# pcb.net
KiCad netlist of a schematic drawn in EAGLE
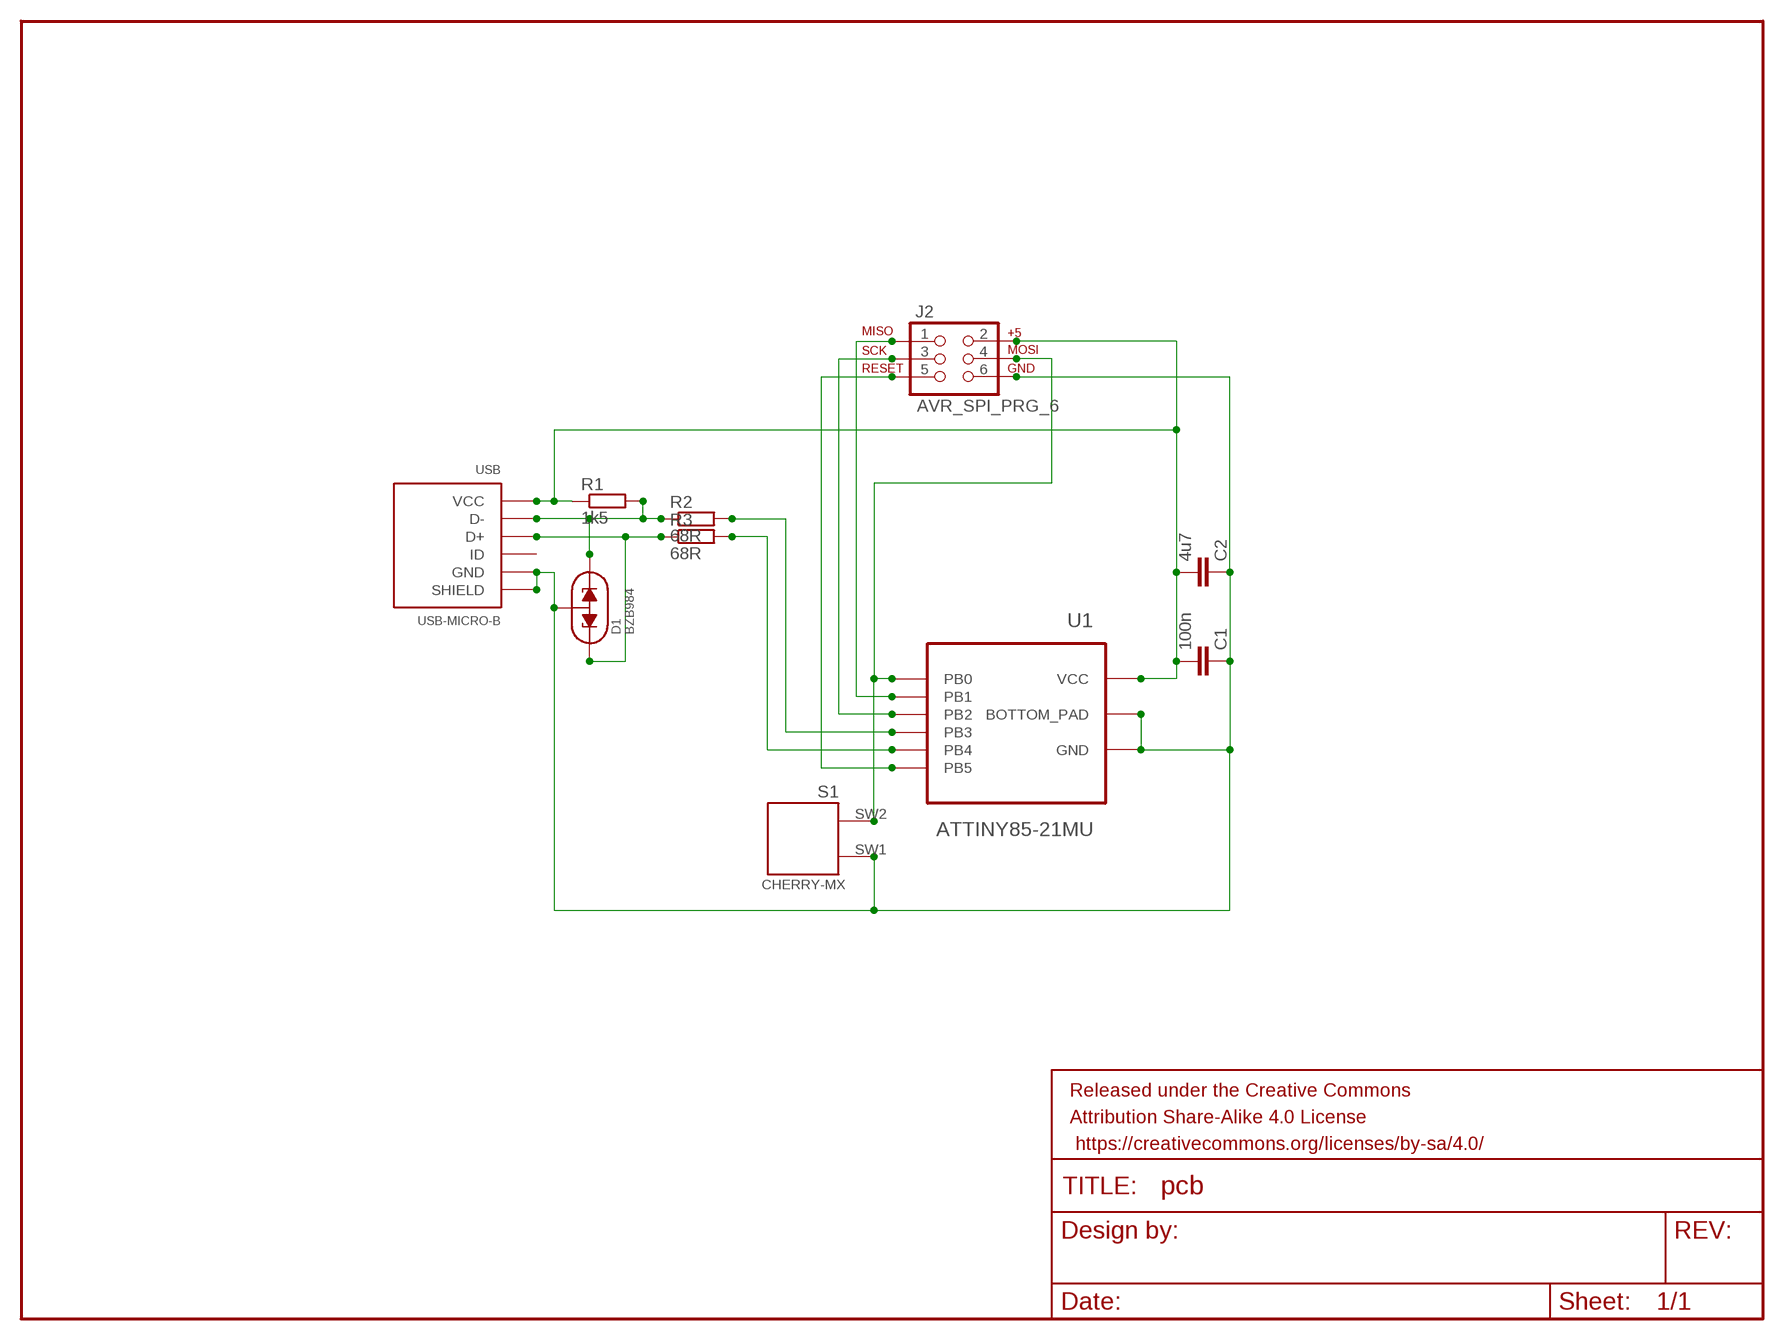
[diagram p0: schematic, sheet 1]

(export (version "E")
  (design (tool "Eeschema 10.0.6"))
  (components
    (comp (ref "C1")
      (value "100n")
      (footprint "eagle-import:C0603")
      (libsource (lib "eagle-import") (part "C-EUC0603"))
    )
    (comp (ref "C2")
      (value "4u7")
      (footprint "eagle-import:C0603")
      (libsource (lib "eagle-import") (part "C-EUC0603"))
    )
    (comp (ref "D1")
      (value "BZB984")
      (footprint "eagle-import:SOT663")
      (libsource (lib "eagle-import") (part "BZB984"))
    )
    (comp (ref "FRAME1")
      (value "FRAME-LETTERNO_PACKAGE")
      (footprint "eagle-import:DUMMY")
      (fields (field (name "DESIGNER") "Nobody"))
      (libsource (lib "eagle-import") (part "FRAME-LETTERNO_PACKAGE"))
    )
    (comp (ref "J2")
      (value "AVR_SPI_PRG_6")
      (footprint "eagle-import:2X3_PADS")
      (libsource (lib "eagle-import") (part "AVR_SPI_PRG_6"))
    )
    (comp (ref "R1")
      (value "1k5")
      (footprint "eagle-import:R0603")
      (libsource (lib "eagle-import") (part "R-EU_R0603"))
    )
    (comp (ref "R2")
      (value "68R")
      (footprint "eagle-import:R0603")
      (libsource (lib "eagle-import") (part "R-EU_R0603"))
    )
    (comp (ref "R3")
      (value "68R")
      (footprint "eagle-import:R0603")
      (libsource (lib "eagle-import") (part "R-EU_R0603"))
    )
    (comp (ref "S1")
      (value "CHERRY-MX-PLATE")
      (footprint "eagle-import:CHERRY-MX-PLATE")
      (libsource (lib "eagle-import") (part "CHERRY-MX-PLATE"))
    )
    (comp (ref "U1")
      (value "ATTINY85-21MU")
      (footprint "eagle-import:QFN-20-4MM")
      (libsource (lib "eagle-import") (part "ATTINY85-21MU"))
    )
    (comp (ref "USB")
      (value "USB-MICRO-B")
      (footprint "eagle-import:MICRO-USB-B")
      (libsource (lib "eagle-import") (part "USB-MICRO-B"))
    )
  )
  (nets
    (net (code "1") (name "Net-(D1-ANODE)") (class "Default")
      (node (ref "C1") (pin "1") (pinfunction "1_1") (pintype "passive"))
      (node (ref "C2") (pin "1") (pinfunction "1_1") (pintype "passive"))
      (node (ref "D1") (pin "3") (pinfunction "ANODE_3") (pintype "bidirectional"))
      (node (ref "J2") (pin "6") (pinfunction "6_6") (pintype "passive"))
      (node (ref "S1") (pin "SW1") (pinfunction "PIN-1_SW1") (pintype "bidirectional"))
      (node (ref "U1") (pin "21") (pinfunction "BOTTOM_PAD_21") (pintype "passive"))
      (node (ref "U1") (pin "8") (pinfunction "GND_8") (pintype "power_in"))
      (node (ref "USB") (pin "5") (pinfunction "GND_5") (pintype "power_in"))
      (node (ref "USB") (pin "P$1") (pinfunction "SHIELD_P$1") (pintype "passive"))
      (node (ref "USB") (pin "P$2") (pinfunction "SHIELD_P$2") (pintype "passive"))
      (node (ref "USB") (pin "P$3") (pinfunction "SHIELD_P$3") (pintype "passive"))
      (node (ref "USB") (pin "P$4") (pinfunction "SHIELD_P$4") (pintype "passive"))
      (node (ref "USB") (pin "SHIELD1") (pinfunction "SHIELD_SHIELD1") (pintype "passive"))
      (node (ref "USB") (pin "SHIELD2") (pinfunction "SHIELD_SHIELD2") (pintype "passive"))
      (node (ref "USB") (pin "SHIELD3") (pinfunction "SHIELD_SHIELD3") (pintype "passive"))
      (node (ref "USB") (pin "SHIELD3A") (pinfunction "SHIELD_SHIELD3A") (pintype "passive"))
      (node (ref "USB") (pin "SHIELD4") (pinfunction "SHIELD_SHIELD4") (pintype "passive"))
      (node (ref "USB") (pin "SHIELD5") (pinfunction "SHIELD_SHIELD5") (pintype "passive"))
      (node (ref "USB") (pin "SHIELD6") (pinfunction "SHIELD_SHIELD6") (pintype "passive"))
      (node (ref "USB") (pin "SHIELD6A") (pinfunction "SHIELD_SHIELD6A") (pintype "passive"))
    )
    (net (code "2") (name "Net-(D1-CATHODE1)") (class "Default")
      (node (ref "D1") (pin "1") (pinfunction "CATHODE1_1") (pintype "bidirectional"))
      (node (ref "R3") (pin "1") (pinfunction "1_1") (pintype "passive"))
      (node (ref "USB") (pin "3") (pinfunction "D+_3") (pintype "bidirectional"))
    )
    (net (code "3") (name "Net-(D1-CATHODE2)") (class "Default")
      (node (ref "D1") (pin "2") (pinfunction "CATHODE2_2") (pintype "bidirectional"))
      (node (ref "R1") (pin "2") (pinfunction "2_2") (pintype "passive"))
      (node (ref "R2") (pin "1") (pinfunction "1_1") (pintype "passive"))
      (node (ref "USB") (pin "2") (pinfunction "D-_2") (pintype "bidirectional"))
    )
    (net (code "4") (name "Net-(S1-PIN-2)") (class "Default")
      (node (ref "J2") (pin "4") (pinfunction "4_4") (pintype "passive"))
      (node (ref "S1") (pin "SW2") (pinfunction "PIN-2_SW2") (pintype "bidirectional"))
      (node (ref "U1") (pin "11") (pinfunction "PB0_11") (pintype "bidirectional"))
    )
    (net (code "5") (name "Net-(U1-PB1)") (class "Default")
      (node (ref "J2") (pin "1") (pinfunction "1_1") (pintype "passive"))
      (node (ref "U1") (pin "12") (pinfunction "PB1_12") (pintype "bidirectional"))
    )
    (net (code "6") (name "Net-(U1-PB2)") (class "Default")
      (node (ref "J2") (pin "3") (pinfunction "3_3") (pintype "passive"))
      (node (ref "U1") (pin "14") (pinfunction "PB2_14") (pintype "bidirectional"))
    )
    (net (code "7") (name "Net-(U1-PB3)") (class "Default")
      (node (ref "R2") (pin "2") (pinfunction "2_2") (pintype "passive"))
      (node (ref "U1") (pin "2") (pinfunction "PB3_2") (pintype "bidirectional"))
    )
    (net (code "8") (name "Net-(U1-PB4)") (class "Default")
      (node (ref "R3") (pin "2") (pinfunction "2_2") (pintype "passive"))
      (node (ref "U1") (pin "5") (pinfunction "PB4_5") (pintype "bidirectional"))
    )
    (net (code "9") (name "Net-(U1-PB5)") (class "Default")
      (node (ref "J2") (pin "5") (pinfunction "5_5") (pintype "passive"))
      (node (ref "U1") (pin "1") (pinfunction "PB5_1") (pintype "bidirectional"))
    )
    (net (code "10") (name "Net-(U1-VCC)") (class "Default")
      (node (ref "C1") (pin "2") (pinfunction "2_2") (pintype "passive"))
      (node (ref "C2") (pin "2") (pinfunction "2_2") (pintype "passive"))
      (node (ref "J2") (pin "2") (pinfunction "2_2") (pintype "passive"))
      (node (ref "R1") (pin "1") (pinfunction "1_1") (pintype "passive"))
      (node (ref "U1") (pin "15") (pinfunction "VCC_15") (pintype "power_in"))
      (node (ref "USB") (pin "1") (pinfunction "VCC_1") (pintype "power_in"))
    )
    (net (code "11") (name "unconnected-(USB-ID-Pad4)") (class "Default")
      (node (ref "USB") (pin "4") (pinfunction "ID_4") (pintype "bidirectional"))
    )
  )
)
